# blink1mk3_micro1e_4l.net
KiCad netlist of a schematic drawn in EAGLE
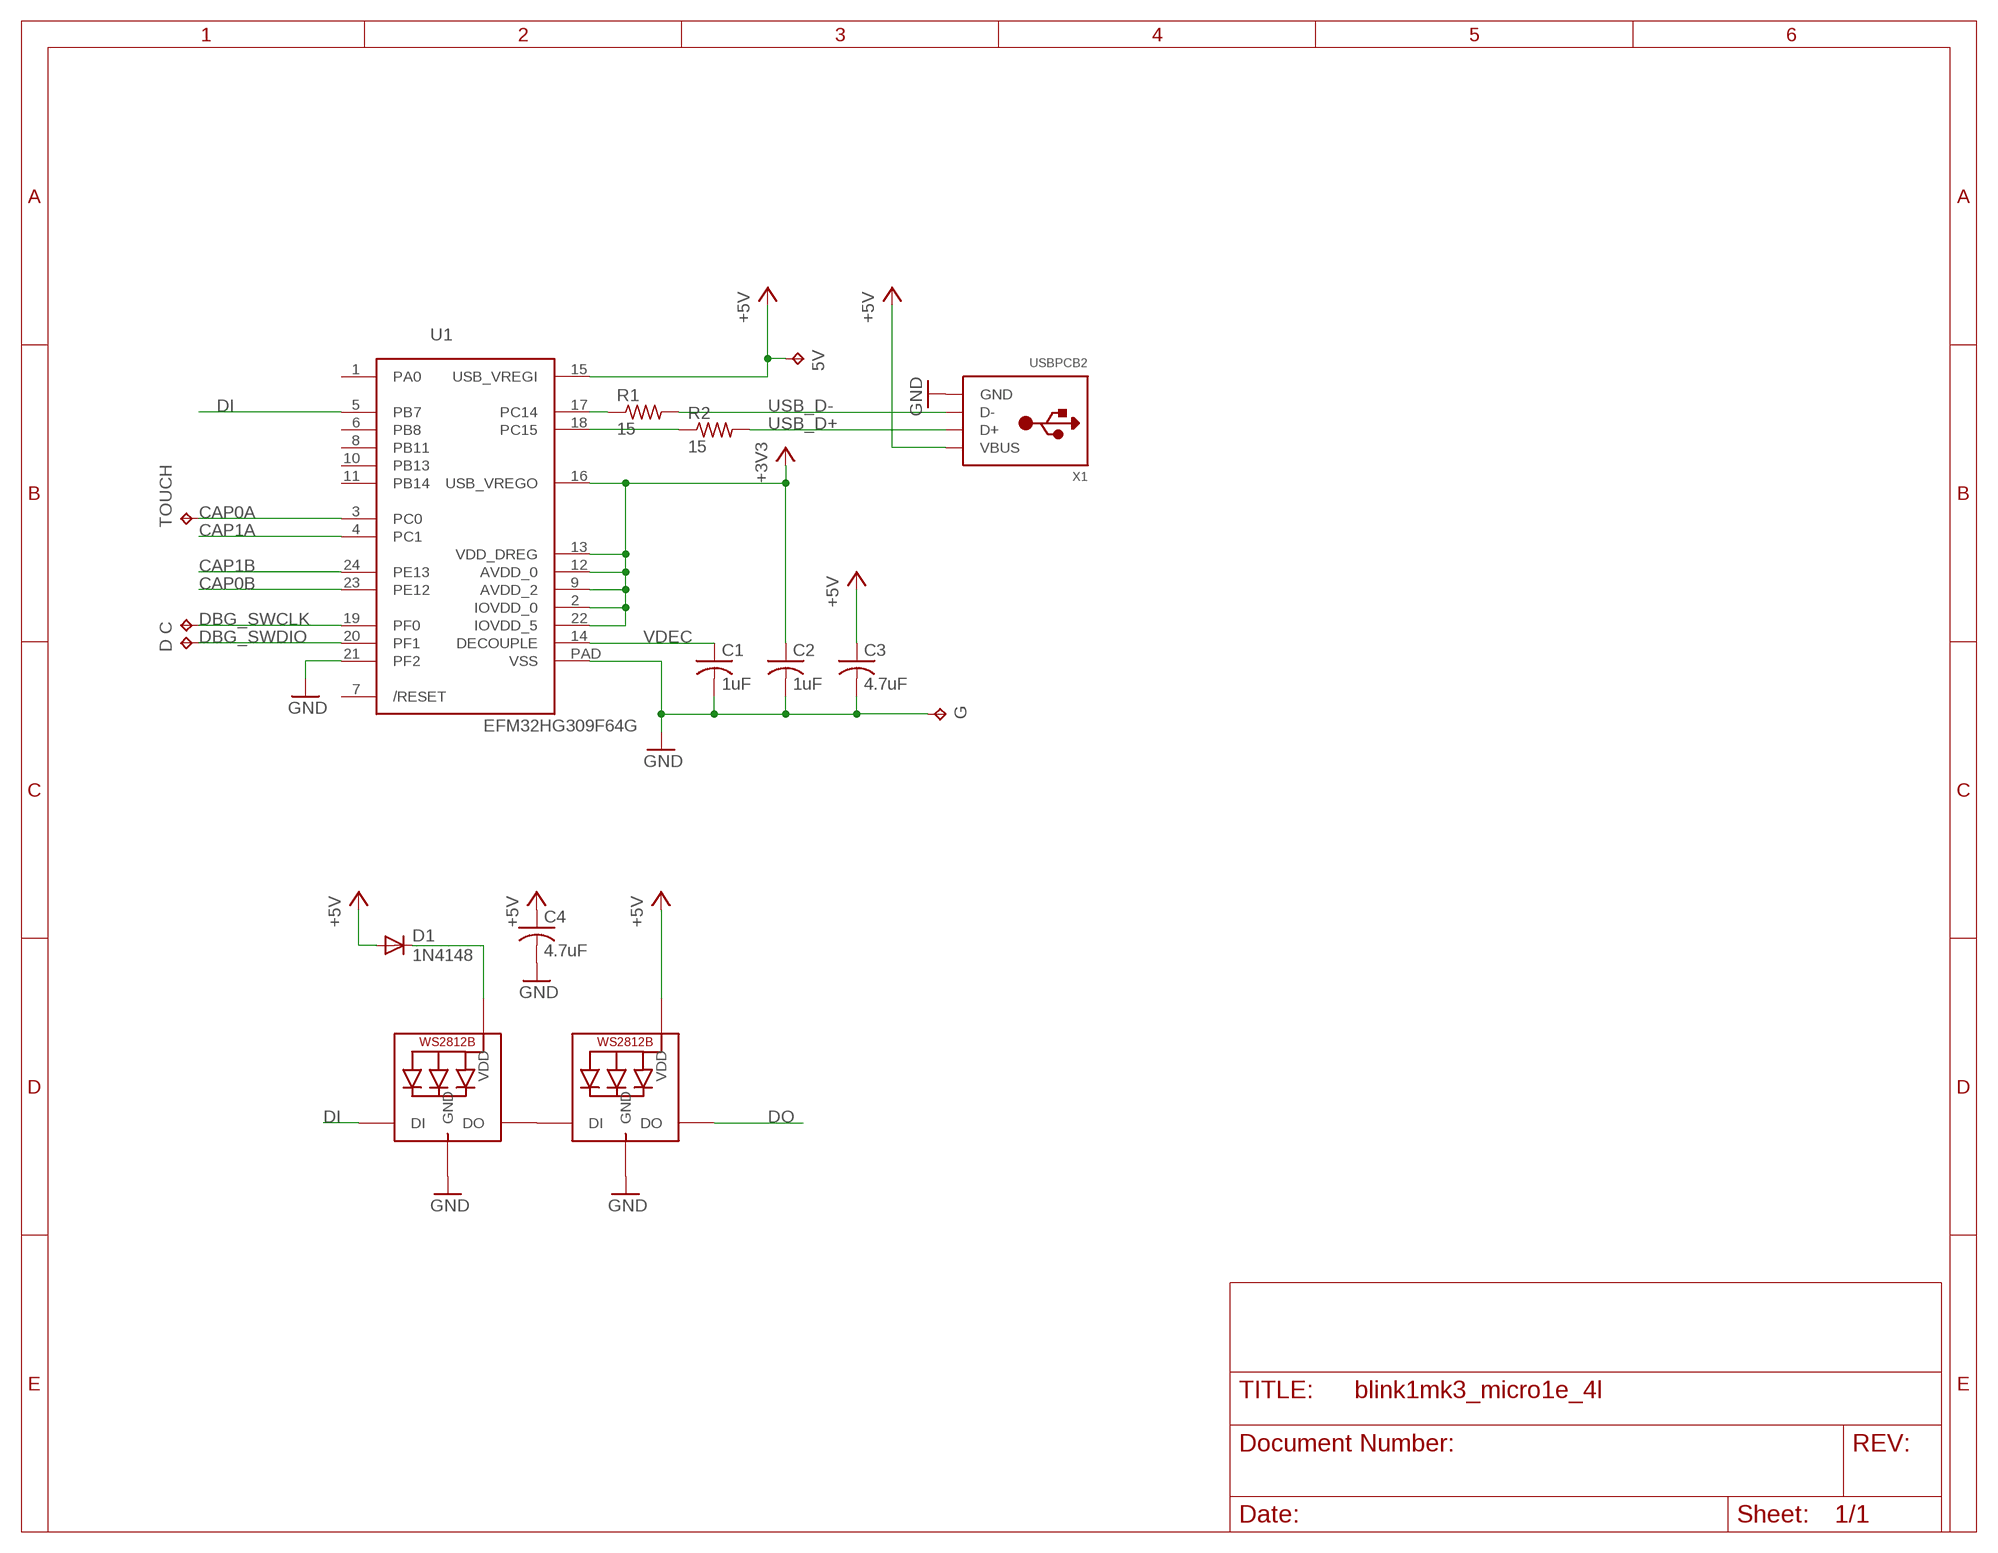
[diagram p0: schematic, sheet 1]

(export (version "E")
  (design (tool "Eeschema 10.0.6"))
  (components
    (comp (ref "5V")
      (value "TPTP10R")
      (footprint "eagle-import:TP10R")
      (libsource (lib "eagle-import") (part "TPTP10R"))
    )
    (comp (ref "C")
      (value "TPTP10R")
      (footprint "eagle-import:TP10R")
      (libsource (lib "eagle-import") (part "TPTP10R"))
    )
    (comp (ref "C1")
      (value "1uF")
      (footprint "eagle-import:C0402")
      (libsource (lib "eagle-import") (part "C-USC0402"))
    )
    (comp (ref "C2")
      (value "1uF")
      (footprint "eagle-import:C0402")
      (libsource (lib "eagle-import") (part "C-USC0402"))
    )
    (comp (ref "C3")
      (value "4.7uF")
      (footprint "eagle-import:C0402")
      (libsource (lib "eagle-import") (part "C-USC0402"))
    )
    (comp (ref "C4")
      (value "4.7uF")
      (footprint "eagle-import:C0402")
      (libsource (lib "eagle-import") (part "C-USC0402"))
    )
    (comp (ref "D")
      (value "TPTP10R")
      (footprint "eagle-import:TP10R")
      (libsource (lib "eagle-import") (part "TPTP10R"))
    )
    (comp (ref "D1")
      (value "1N4148")
      (footprint "eagle-import:SOD523")
      (libsource (lib "eagle-import") (part "DIODE-SOD523"))
    )
    (comp (ref "G")
      (value "TPTP10SQ")
      (footprint "eagle-import:TP10SQ")
      (libsource (lib "eagle-import") (part "TPTP10SQ"))
    )
    (comp (ref "LED1")
      (value "WS2812B4020SIDE")
      (footprint "eagle-import:SK6812-SIDE")
      (libsource (lib "eagle-import") (part "WS2812B4020SIDE"))
    )
    (comp (ref "LED2")
      (value "WS2812B4020SIDE")
      (footprint "eagle-import:SK6812-SIDE")
      (libsource (lib "eagle-import") (part "WS2812B4020SIDE"))
    )
    (comp (ref "R1")
      (value "15")
      (footprint "eagle-import:R0402")
      (libsource (lib "eagle-import") (part "R-US_R0402"))
    )
    (comp (ref "R2")
      (value "15")
      (footprint "eagle-import:R0402")
      (libsource (lib "eagle-import") (part "R-US_R0402"))
    )
    (comp (ref "TOUCH")
      (value "TPTP10R")
      (footprint "eagle-import:TP10R")
      (libsource (lib "eagle-import") (part "TPTP10R"))
    )
    (comp (ref "U1")
      (value "EFM32HG309F64G")
      (footprint "eagle-import:QFN24PAD")
      (libsource (lib "eagle-import") (part "EFM32HG309F64G"))
    )
    (comp (ref "X1")
      (value "USBPCB2")
      (footprint "eagle-import:USB-A-PCB-2")
      (libsource (lib "eagle-import") (part "USBPCB2"))
    )
  )
  (nets
    (net (code "1") (name "+3V3") (class "Default")
      (node (ref "C2") (pin "1") (pinfunction "1_1") (pintype "passive"))
      (node (ref "U1") (pin "12") (pinfunction "AVDD_0_12") (pintype "bidirectional"))
      (node (ref "U1") (pin "13") (pinfunction "VDD_DREG_13") (pintype "bidirectional"))
      (node (ref "U1") (pin "16") (pinfunction "USB_VREGO_16") (pintype "bidirectional"))
      (node (ref "U1") (pin "2") (pinfunction "IOVDD_0_2") (pintype "bidirectional"))
      (node (ref "U1") (pin "22") (pinfunction "IOVDD_5_22") (pintype "bidirectional"))
      (node (ref "U1") (pin "9") (pinfunction "AVDD_2_9") (pintype "bidirectional"))
    )
    (net (code "2") (name "+5V") (class "Default")
      (node (ref "5V") (pin "TP") (pinfunction "TP_TP") (pintype "input"))
      (node (ref "C3") (pin "1") (pinfunction "1_1") (pintype "passive"))
      (node (ref "C4") (pin "1") (pinfunction "1_1") (pintype "passive"))
      (node (ref "D1") (pin "A") (pinfunction "A_A") (pintype "passive"))
      (node (ref "LED2") (pin "1-VDD") (pinfunction "VDD_1-VDD") (pintype "power_in"))
      (node (ref "U1") (pin "15") (pinfunction "USB_VREGI_15") (pintype "bidirectional"))
      (node (ref "X1") (pin "5V") (pinfunction "VBUS_5V") (pintype "power_in"))
    )
    (net (code "3") (name "/CAP0A") (class "Default")
      (node (ref "TOUCH") (pin "TP") (pinfunction "TP_TP") (pintype "input"))
      (node (ref "U1") (pin "3") (pinfunction "PC0_3") (pintype "bidirectional"))
    )
    (net (code "4") (name "/CAP0B") (class "Default")
      (node (ref "U1") (pin "23") (pinfunction "PE12_23") (pintype "bidirectional"))
    )
    (net (code "5") (name "/CAP1A") (class "Default")
      (node (ref "U1") (pin "4") (pinfunction "PC1_4") (pintype "bidirectional"))
    )
    (net (code "6") (name "/CAP1B") (class "Default")
      (node (ref "U1") (pin "24") (pinfunction "PE13_24") (pintype "bidirectional"))
    )
    (net (code "7") (name "/DBG_SWCLK") (class "Default")
      (node (ref "C") (pin "TP") (pinfunction "TP_TP") (pintype "input"))
      (node (ref "U1") (pin "19") (pinfunction "PF0_19") (pintype "bidirectional"))
    )
    (net (code "8") (name "/DBG_SWDIO") (class "Default")
      (node (ref "D") (pin "TP") (pinfunction "TP_TP") (pintype "input"))
      (node (ref "U1") (pin "20") (pinfunction "PF1_20") (pintype "bidirectional"))
    )
    (net (code "9") (name "/DI") (class "Default")
      (node (ref "LED1") (pin "4-DIN") (pinfunction "DI_4-DIN") (pintype "input"))
      (node (ref "U1") (pin "5") (pinfunction "PB7_5") (pintype "bidirectional"))
    )
    (net (code "10") (name "/DO") (class "Default")
      (node (ref "LED2") (pin "2-DOUT") (pinfunction "DO_2-DOUT") (pintype "output"))
    )
    (net (code "11") (name "/USB_D+") (class "Default")
      (node (ref "R2") (pin "2") (pinfunction "2_2") (pintype "passive"))
      (node (ref "X1") (pin "USB_P") (pinfunction "D+_USB_P") (pintype "bidirectional"))
    )
    (net (code "12") (name "/USB_D-") (class "Default")
      (node (ref "R1") (pin "2") (pinfunction "2_2") (pintype "passive"))
      (node (ref "X1") (pin "USB_M") (pinfunction "D-_USB_M") (pintype "bidirectional"))
    )
    (net (code "13") (name "/VDEC") (class "Default")
      (node (ref "C1") (pin "1") (pinfunction "1_1") (pintype "passive"))
      (node (ref "U1") (pin "14") (pinfunction "DECOUPLE_14") (pintype "bidirectional"))
    )
    (net (code "14") (name "GND") (class "Default")
      (node (ref "C1") (pin "2") (pinfunction "2_2") (pintype "passive"))
      (node (ref "C2") (pin "2") (pinfunction "2_2") (pintype "passive"))
      (node (ref "C3") (pin "2") (pinfunction "2_2") (pintype "passive"))
      (node (ref "C4") (pin "2") (pinfunction "2_2") (pintype "passive"))
      (node (ref "G") (pin "TP") (pinfunction "TP_TP") (pintype "input"))
      (node (ref "LED1") (pin "3-GND") (pinfunction "GND_3-GND") (pintype "power_in"))
      (node (ref "LED2") (pin "3-GND") (pinfunction "GND_3-GND") (pintype "power_in"))
      (node (ref "U1") (pin "21") (pinfunction "PF2_21") (pintype "bidirectional"))
      (node (ref "U1") (pin "PAD") (pinfunction "VSS_PAD") (pintype "bidirectional"))
      (node (ref "X1") (pin "GND") (pinfunction "GND_GND") (pintype "power_in"))
    )
    (net (code "15") (name "Net-(LED1-DO)") (class "Default")
      (node (ref "LED1") (pin "2-DOUT") (pinfunction "DO_2-DOUT") (pintype "output"))
      (node (ref "LED2") (pin "4-DIN") (pinfunction "DI_4-DIN") (pintype "input"))
    )
    (net (code "16") (name "Net-(LED1-VDD)") (class "Default")
      (node (ref "D1") (pin "C") (pinfunction "C_C") (pintype "passive"))
      (node (ref "LED1") (pin "1-VDD") (pinfunction "VDD_1-VDD") (pintype "power_in"))
    )
    (net (code "17") (name "Net-(U1-PC14)") (class "Default")
      (node (ref "R1") (pin "1") (pinfunction "1_1") (pintype "passive"))
      (node (ref "U1") (pin "17") (pinfunction "PC14_17") (pintype "bidirectional"))
    )
    (net (code "18") (name "Net-(U1-PC15)") (class "Default")
      (node (ref "R2") (pin "1") (pinfunction "1_1") (pintype "passive"))
      (node (ref "U1") (pin "18") (pinfunction "PC15_18") (pintype "bidirectional"))
    )
    (net (code "19") (name "unconnected-(U1-PA0-Pad1)") (class "Default")
      (node (ref "U1") (pin "1") (pinfunction "PA0_1") (pintype "bidirectional"))
    )
    (net (code "20") (name "unconnected-(U1-PB8-Pad6)") (class "Default")
      (node (ref "U1") (pin "6") (pinfunction "PB8_6") (pintype "bidirectional"))
    )
    (net (code "21") (name "unconnected-(U1-PB11-Pad8)") (class "Default")
      (node (ref "U1") (pin "8") (pinfunction "PB11_8") (pintype "bidirectional"))
    )
    (net (code "22") (name "unconnected-(U1-PB13-Pad10)") (class "Default")
      (node (ref "U1") (pin "10") (pinfunction "PB13_10") (pintype "bidirectional"))
    )
    (net (code "23") (name "unconnected-(U1-PB14-Pad11)") (class "Default")
      (node (ref "U1") (pin "11") (pinfunction "PB14_11") (pintype "bidirectional"))
    )
    (net (code "24") (name "unconnected-(U1-{slash}RESET-Pad7)") (class "Default")
      (node (ref "U1") (pin "7") (pinfunction "/RESET_7") (pintype "bidirectional"))
    )
  )
)
